# 2_dsub_to_pins_quick.net
KiCad netlist of a schematic drawn in EAGLE
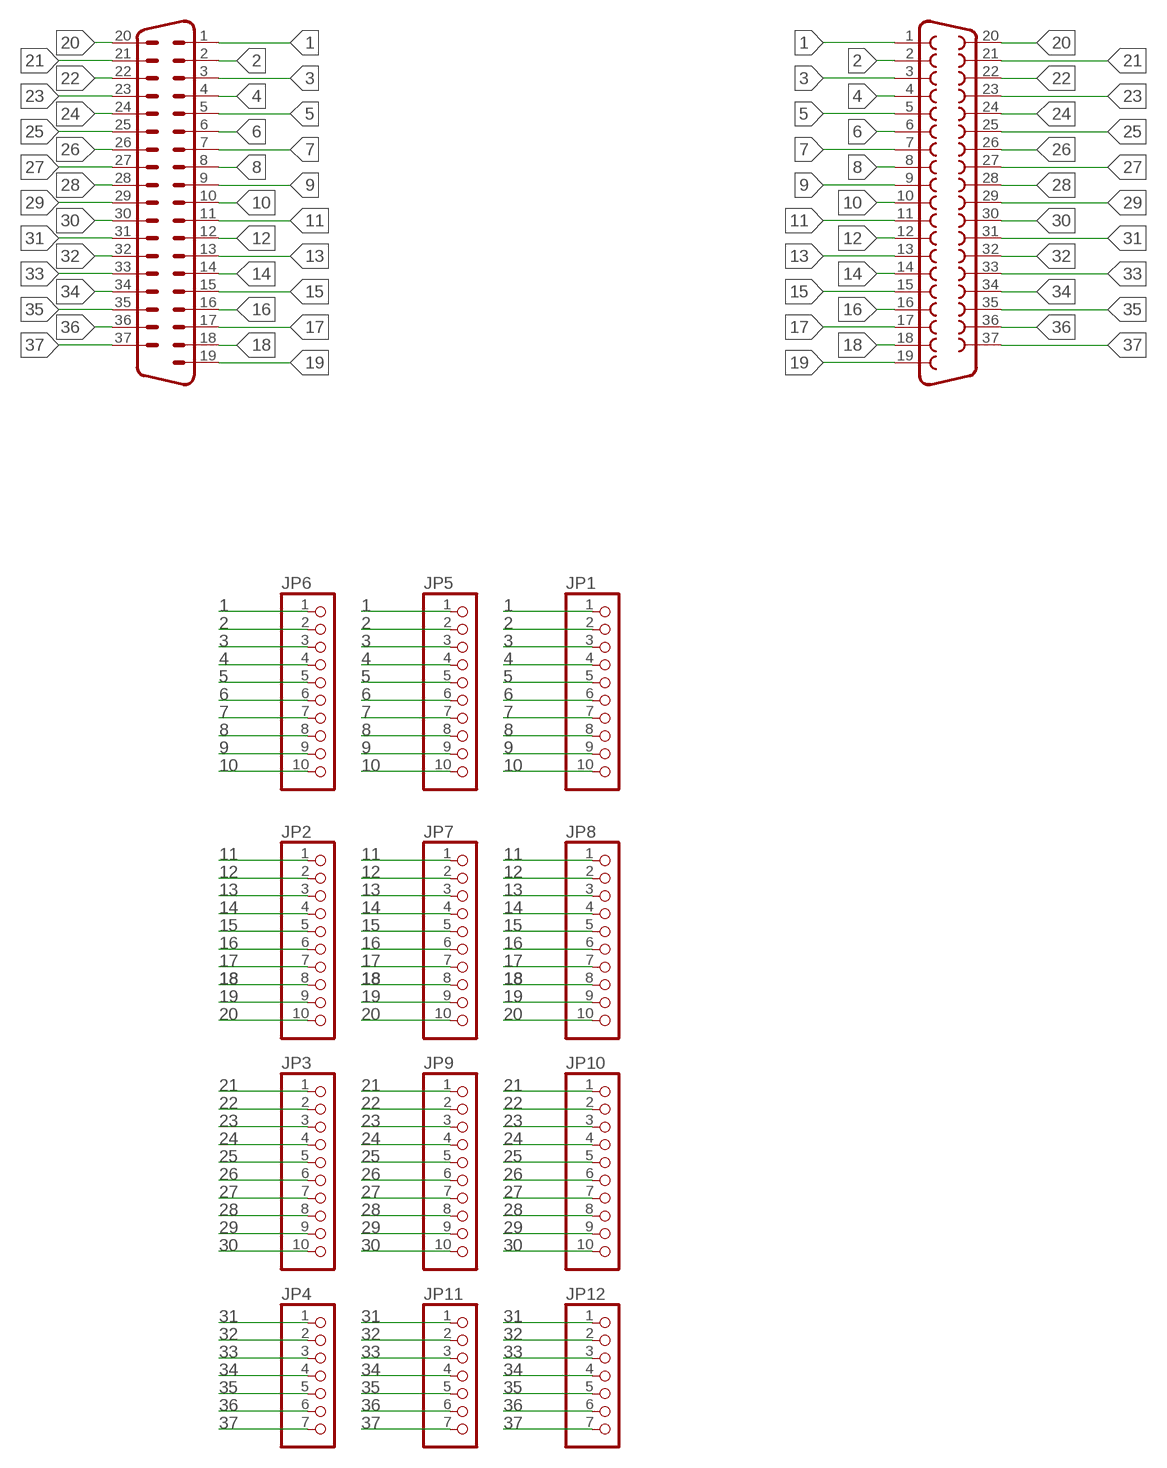
[diagram p0: schematic, sheet 1]

(export (version "E")
  (design (tool "Eeschema 10.0.6"))
  (components
    (comp (ref "JP1")
      (value "PINHD-1X10")
      (footprint "eagle-import:1X10")
      (libsource (lib "eagle-import") (part "PINHD-1X10"))
    )
    (comp (ref "JP2")
      (value "PINHD-1X10")
      (footprint "eagle-import:1X10")
      (libsource (lib "eagle-import") (part "PINHD-1X10"))
    )
    (comp (ref "JP3")
      (value "PINHD-1X10")
      (footprint "eagle-import:1X10")
      (libsource (lib "eagle-import") (part "PINHD-1X10"))
    )
    (comp (ref "JP4")
      (value "PINHD-1X7")
      (footprint "eagle-import:1X07")
      (libsource (lib "eagle-import") (part "PINHD-1X7"))
    )
    (comp (ref "JP5")
      (value "PINHD-1X10")
      (footprint "eagle-import:1X10")
      (libsource (lib "eagle-import") (part "PINHD-1X10"))
    )
    (comp (ref "JP6")
      (value "PINHD-1X10")
      (footprint "eagle-import:1X10")
      (libsource (lib "eagle-import") (part "PINHD-1X10"))
    )
    (comp (ref "JP7")
      (value "PINHD-1X10")
      (footprint "eagle-import:1X10")
      (libsource (lib "eagle-import") (part "PINHD-1X10"))
    )
    (comp (ref "JP8")
      (value "PINHD-1X10")
      (footprint "eagle-import:1X10")
      (libsource (lib "eagle-import") (part "PINHD-1X10"))
    )
    (comp (ref "JP9")
      (value "PINHD-1X10")
      (footprint "eagle-import:1X10")
      (libsource (lib "eagle-import") (part "PINHD-1X10"))
    )
    (comp (ref "JP10")
      (value "PINHD-1X10")
      (footprint "eagle-import:1X10")
      (libsource (lib "eagle-import") (part "PINHD-1X10"))
    )
    (comp (ref "JP11")
      (value "PINHD-1X7")
      (footprint "eagle-import:1X07")
      (libsource (lib "eagle-import") (part "PINHD-1X7"))
    )
    (comp (ref "JP12")
      (value "PINHD-1X7")
      (footprint "eagle-import:1X07")
      (libsource (lib "eagle-import") (part "PINHD-1X7"))
    )
    (comp (ref "X33")
      (value "M37HP")
      (footprint "eagle-import:M37HP")
      (libsource (lib "eagle-import") (part "M37HP"))
    )
    (comp (ref "X34")
      (value "F37HP")
      (footprint "eagle-import:F37HP")
      (libsource (lib "eagle-import") (part "F37HP"))
    )
  )
  (nets
    (net (code "1") (name "1") (class "Default")
      (node (ref "JP1") (pin "1") (pinfunction "1_1") (pintype "passive"))
      (node (ref "JP5") (pin "1") (pinfunction "1_1") (pintype "passive"))
      (node (ref "JP6") (pin "1") (pinfunction "1_1") (pintype "passive"))
      (node (ref "X33") (pin "1") (pinfunction "1_1") (pintype "passive"))
      (node (ref "X34") (pin "1") (pinfunction "1_1") (pintype "passive"))
    )
    (net (code "2") (name "2") (class "Default")
      (node (ref "JP1") (pin "2") (pinfunction "2_2") (pintype "passive"))
      (node (ref "JP5") (pin "2") (pinfunction "2_2") (pintype "passive"))
      (node (ref "JP6") (pin "2") (pinfunction "2_2") (pintype "passive"))
      (node (ref "X33") (pin "2") (pinfunction "2_2") (pintype "passive"))
      (node (ref "X34") (pin "2") (pinfunction "2_2") (pintype "passive"))
    )
    (net (code "3") (name "3") (class "Default")
      (node (ref "JP1") (pin "3") (pinfunction "3_3") (pintype "passive"))
      (node (ref "JP5") (pin "3") (pinfunction "3_3") (pintype "passive"))
      (node (ref "JP6") (pin "3") (pinfunction "3_3") (pintype "passive"))
      (node (ref "X33") (pin "3") (pinfunction "3_3") (pintype "passive"))
      (node (ref "X34") (pin "3") (pinfunction "3_3") (pintype "passive"))
    )
    (net (code "4") (name "4") (class "Default")
      (node (ref "JP1") (pin "4") (pinfunction "4_4") (pintype "passive"))
      (node (ref "JP5") (pin "4") (pinfunction "4_4") (pintype "passive"))
      (node (ref "JP6") (pin "4") (pinfunction "4_4") (pintype "passive"))
      (node (ref "X33") (pin "4") (pinfunction "4_4") (pintype "passive"))
      (node (ref "X34") (pin "4") (pinfunction "4_4") (pintype "passive"))
    )
    (net (code "5") (name "5") (class "Default")
      (node (ref "JP1") (pin "5") (pinfunction "5_5") (pintype "passive"))
      (node (ref "JP5") (pin "5") (pinfunction "5_5") (pintype "passive"))
      (node (ref "JP6") (pin "5") (pinfunction "5_5") (pintype "passive"))
      (node (ref "X33") (pin "5") (pinfunction "5_5") (pintype "passive"))
      (node (ref "X34") (pin "5") (pinfunction "5_5") (pintype "passive"))
    )
    (net (code "6") (name "6") (class "Default")
      (node (ref "JP1") (pin "6") (pinfunction "6_6") (pintype "passive"))
      (node (ref "JP5") (pin "6") (pinfunction "6_6") (pintype "passive"))
      (node (ref "JP6") (pin "6") (pinfunction "6_6") (pintype "passive"))
      (node (ref "X33") (pin "6") (pinfunction "6_6") (pintype "passive"))
      (node (ref "X34") (pin "6") (pinfunction "6_6") (pintype "passive"))
    )
    (net (code "7") (name "7") (class "Default")
      (node (ref "JP1") (pin "7") (pinfunction "7_7") (pintype "passive"))
      (node (ref "JP5") (pin "7") (pinfunction "7_7") (pintype "passive"))
      (node (ref "JP6") (pin "7") (pinfunction "7_7") (pintype "passive"))
      (node (ref "X33") (pin "7") (pinfunction "7_7") (pintype "passive"))
      (node (ref "X34") (pin "7") (pinfunction "7_7") (pintype "passive"))
    )
    (net (code "8") (name "8") (class "Default")
      (node (ref "JP1") (pin "8") (pinfunction "8_8") (pintype "passive"))
      (node (ref "JP5") (pin "8") (pinfunction "8_8") (pintype "passive"))
      (node (ref "JP6") (pin "8") (pinfunction "8_8") (pintype "passive"))
      (node (ref "X33") (pin "8") (pinfunction "8_8") (pintype "passive"))
      (node (ref "X34") (pin "8") (pinfunction "8_8") (pintype "passive"))
    )
    (net (code "9") (name "9") (class "Default")
      (node (ref "JP1") (pin "9") (pinfunction "9_9") (pintype "passive"))
      (node (ref "JP5") (pin "9") (pinfunction "9_9") (pintype "passive"))
      (node (ref "JP6") (pin "9") (pinfunction "9_9") (pintype "passive"))
      (node (ref "X33") (pin "9") (pinfunction "9_9") (pintype "passive"))
      (node (ref "X34") (pin "9") (pinfunction "9_9") (pintype "passive"))
    )
    (net (code "10") (name "10") (class "Default")
      (node (ref "JP1") (pin "10") (pinfunction "10_10") (pintype "passive"))
      (node (ref "JP5") (pin "10") (pinfunction "10_10") (pintype "passive"))
      (node (ref "JP6") (pin "10") (pinfunction "10_10") (pintype "passive"))
      (node (ref "X33") (pin "10") (pinfunction "10_10") (pintype "passive"))
      (node (ref "X34") (pin "10") (pinfunction "10_10") (pintype "passive"))
    )
    (net (code "11") (name "11") (class "Default")
      (node (ref "JP2") (pin "1") (pinfunction "1_1") (pintype "passive"))
      (node (ref "JP7") (pin "1") (pinfunction "1_1") (pintype "passive"))
      (node (ref "JP8") (pin "1") (pinfunction "1_1") (pintype "passive"))
      (node (ref "X33") (pin "11") (pinfunction "11_11") (pintype "passive"))
      (node (ref "X34") (pin "11") (pinfunction "11_11") (pintype "passive"))
    )
    (net (code "12") (name "12") (class "Default")
      (node (ref "JP2") (pin "2") (pinfunction "2_2") (pintype "passive"))
      (node (ref "JP7") (pin "2") (pinfunction "2_2") (pintype "passive"))
      (node (ref "JP8") (pin "2") (pinfunction "2_2") (pintype "passive"))
      (node (ref "X33") (pin "12") (pinfunction "12_12") (pintype "passive"))
      (node (ref "X34") (pin "12") (pinfunction "12_12") (pintype "passive"))
    )
    (net (code "13") (name "13") (class "Default")
      (node (ref "JP2") (pin "3") (pinfunction "3_3") (pintype "passive"))
      (node (ref "JP7") (pin "3") (pinfunction "3_3") (pintype "passive"))
      (node (ref "JP8") (pin "3") (pinfunction "3_3") (pintype "passive"))
      (node (ref "X33") (pin "13") (pinfunction "13_13") (pintype "passive"))
      (node (ref "X34") (pin "13") (pinfunction "13_13") (pintype "passive"))
    )
    (net (code "14") (name "14") (class "Default")
      (node (ref "JP2") (pin "4") (pinfunction "4_4") (pintype "passive"))
      (node (ref "JP7") (pin "4") (pinfunction "4_4") (pintype "passive"))
      (node (ref "JP8") (pin "4") (pinfunction "4_4") (pintype "passive"))
      (node (ref "X33") (pin "14") (pinfunction "14_14") (pintype "passive"))
      (node (ref "X34") (pin "14") (pinfunction "14_14") (pintype "passive"))
    )
    (net (code "15") (name "15") (class "Default")
      (node (ref "JP2") (pin "5") (pinfunction "5_5") (pintype "passive"))
      (node (ref "JP7") (pin "5") (pinfunction "5_5") (pintype "passive"))
      (node (ref "JP8") (pin "5") (pinfunction "5_5") (pintype "passive"))
      (node (ref "X33") (pin "15") (pinfunction "15_15") (pintype "passive"))
      (node (ref "X34") (pin "15") (pinfunction "15_15") (pintype "passive"))
    )
    (net (code "16") (name "16") (class "Default")
      (node (ref "JP2") (pin "6") (pinfunction "6_6") (pintype "passive"))
      (node (ref "JP7") (pin "6") (pinfunction "6_6") (pintype "passive"))
      (node (ref "JP8") (pin "6") (pinfunction "6_6") (pintype "passive"))
      (node (ref "X33") (pin "16") (pinfunction "16_16") (pintype "passive"))
      (node (ref "X34") (pin "16") (pinfunction "16_16") (pintype "passive"))
    )
    (net (code "17") (name "17") (class "Default")
      (node (ref "JP2") (pin "7") (pinfunction "7_7") (pintype "passive"))
      (node (ref "JP7") (pin "7") (pinfunction "7_7") (pintype "passive"))
      (node (ref "JP8") (pin "7") (pinfunction "7_7") (pintype "passive"))
      (node (ref "X33") (pin "17") (pinfunction "17_17") (pintype "passive"))
      (node (ref "X34") (pin "17") (pinfunction "17_17") (pintype "passive"))
    )
    (net (code "18") (name "18") (class "Default")
      (node (ref "JP2") (pin "8") (pinfunction "8_8") (pintype "passive"))
      (node (ref "JP7") (pin "8") (pinfunction "8_8") (pintype "passive"))
      (node (ref "JP8") (pin "8") (pinfunction "8_8") (pintype "passive"))
      (node (ref "X33") (pin "18") (pinfunction "18_18") (pintype "passive"))
      (node (ref "X34") (pin "18") (pinfunction "18_18") (pintype "passive"))
    )
    (net (code "19") (name "19") (class "Default")
      (node (ref "JP2") (pin "9") (pinfunction "9_9") (pintype "passive"))
      (node (ref "JP7") (pin "9") (pinfunction "9_9") (pintype "passive"))
      (node (ref "JP8") (pin "9") (pinfunction "9_9") (pintype "passive"))
      (node (ref "X33") (pin "19") (pinfunction "19_19") (pintype "passive"))
      (node (ref "X34") (pin "19") (pinfunction "19_19") (pintype "passive"))
    )
    (net (code "20") (name "20") (class "Default")
      (node (ref "JP2") (pin "10") (pinfunction "10_10") (pintype "passive"))
      (node (ref "JP7") (pin "10") (pinfunction "10_10") (pintype "passive"))
      (node (ref "JP8") (pin "10") (pinfunction "10_10") (pintype "passive"))
      (node (ref "X33") (pin "20") (pinfunction "20_20") (pintype "passive"))
      (node (ref "X34") (pin "20") (pinfunction "20_20") (pintype "passive"))
    )
    (net (code "21") (name "21") (class "Default")
      (node (ref "JP10") (pin "1") (pinfunction "1_1") (pintype "passive"))
      (node (ref "JP3") (pin "1") (pinfunction "1_1") (pintype "passive"))
      (node (ref "JP9") (pin "1") (pinfunction "1_1") (pintype "passive"))
      (node (ref "X33") (pin "21") (pinfunction "21_21") (pintype "passive"))
      (node (ref "X34") (pin "21") (pinfunction "21_21") (pintype "passive"))
    )
    (net (code "22") (name "22") (class "Default")
      (node (ref "JP10") (pin "2") (pinfunction "2_2") (pintype "passive"))
      (node (ref "JP3") (pin "2") (pinfunction "2_2") (pintype "passive"))
      (node (ref "JP9") (pin "2") (pinfunction "2_2") (pintype "passive"))
      (node (ref "X33") (pin "22") (pinfunction "22_22") (pintype "passive"))
      (node (ref "X34") (pin "22") (pinfunction "22_22") (pintype "passive"))
    )
    (net (code "23") (name "23") (class "Default")
      (node (ref "JP10") (pin "3") (pinfunction "3_3") (pintype "passive"))
      (node (ref "JP3") (pin "3") (pinfunction "3_3") (pintype "passive"))
      (node (ref "JP9") (pin "3") (pinfunction "3_3") (pintype "passive"))
      (node (ref "X33") (pin "23") (pinfunction "23_23") (pintype "passive"))
      (node (ref "X34") (pin "23") (pinfunction "23_23") (pintype "passive"))
    )
    (net (code "24") (name "24") (class "Default")
      (node (ref "JP10") (pin "4") (pinfunction "4_4") (pintype "passive"))
      (node (ref "JP3") (pin "4") (pinfunction "4_4") (pintype "passive"))
      (node (ref "JP9") (pin "4") (pinfunction "4_4") (pintype "passive"))
      (node (ref "X33") (pin "24") (pinfunction "24_24") (pintype "passive"))
      (node (ref "X34") (pin "24") (pinfunction "24_24") (pintype "passive"))
    )
    (net (code "25") (name "25") (class "Default")
      (node (ref "JP10") (pin "5") (pinfunction "5_5") (pintype "passive"))
      (node (ref "JP3") (pin "5") (pinfunction "5_5") (pintype "passive"))
      (node (ref "JP9") (pin "5") (pinfunction "5_5") (pintype "passive"))
      (node (ref "X33") (pin "25") (pinfunction "25_25") (pintype "passive"))
      (node (ref "X34") (pin "25") (pinfunction "25_25") (pintype "passive"))
    )
    (net (code "26") (name "26") (class "Default")
      (node (ref "JP10") (pin "6") (pinfunction "6_6") (pintype "passive"))
      (node (ref "JP3") (pin "6") (pinfunction "6_6") (pintype "passive"))
      (node (ref "JP9") (pin "6") (pinfunction "6_6") (pintype "passive"))
      (node (ref "X33") (pin "26") (pinfunction "26_26") (pintype "passive"))
      (node (ref "X34") (pin "26") (pinfunction "26_26") (pintype "passive"))
    )
    (net (code "27") (name "27") (class "Default")
      (node (ref "JP10") (pin "7") (pinfunction "7_7") (pintype "passive"))
      (node (ref "JP3") (pin "7") (pinfunction "7_7") (pintype "passive"))
      (node (ref "JP9") (pin "7") (pinfunction "7_7") (pintype "passive"))
      (node (ref "X33") (pin "27") (pinfunction "27_27") (pintype "passive"))
      (node (ref "X34") (pin "27") (pinfunction "27_27") (pintype "passive"))
    )
    (net (code "28") (name "28") (class "Default")
      (node (ref "JP10") (pin "8") (pinfunction "8_8") (pintype "passive"))
      (node (ref "JP3") (pin "8") (pinfunction "8_8") (pintype "passive"))
      (node (ref "JP9") (pin "8") (pinfunction "8_8") (pintype "passive"))
      (node (ref "X33") (pin "28") (pinfunction "28_28") (pintype "passive"))
      (node (ref "X34") (pin "28") (pinfunction "28_28") (pintype "passive"))
    )
    (net (code "29") (name "29") (class "Default")
      (node (ref "JP10") (pin "9") (pinfunction "9_9") (pintype "passive"))
      (node (ref "JP3") (pin "9") (pinfunction "9_9") (pintype "passive"))
      (node (ref "JP9") (pin "9") (pinfunction "9_9") (pintype "passive"))
      (node (ref "X33") (pin "29") (pinfunction "29_29") (pintype "passive"))
      (node (ref "X34") (pin "29") (pinfunction "29_29") (pintype "passive"))
    )
    (net (code "30") (name "30") (class "Default")
      (node (ref "JP10") (pin "10") (pinfunction "10_10") (pintype "passive"))
      (node (ref "JP3") (pin "10") (pinfunction "10_10") (pintype "passive"))
      (node (ref "JP9") (pin "10") (pinfunction "10_10") (pintype "passive"))
      (node (ref "X33") (pin "30") (pinfunction "30_30") (pintype "passive"))
      (node (ref "X34") (pin "30") (pinfunction "30_30") (pintype "passive"))
    )
    (net (code "31") (name "31") (class "Default")
      (node (ref "JP11") (pin "1") (pinfunction "1_1") (pintype "passive"))
      (node (ref "JP12") (pin "1") (pinfunction "1_1") (pintype "passive"))
      (node (ref "JP4") (pin "1") (pinfunction "1_1") (pintype "passive"))
      (node (ref "X33") (pin "31") (pinfunction "31_31") (pintype "passive"))
      (node (ref "X34") (pin "31") (pinfunction "31_31") (pintype "passive"))
    )
    (net (code "32") (name "32") (class "Default")
      (node (ref "JP11") (pin "2") (pinfunction "2_2") (pintype "passive"))
      (node (ref "JP12") (pin "2") (pinfunction "2_2") (pintype "passive"))
      (node (ref "JP4") (pin "2") (pinfunction "2_2") (pintype "passive"))
      (node (ref "X33") (pin "32") (pinfunction "32_32") (pintype "passive"))
      (node (ref "X34") (pin "32") (pinfunction "32_32") (pintype "passive"))
    )
    (net (code "33") (name "33") (class "Default")
      (node (ref "JP11") (pin "3") (pinfunction "3_3") (pintype "passive"))
      (node (ref "JP12") (pin "3") (pinfunction "3_3") (pintype "passive"))
      (node (ref "JP4") (pin "3") (pinfunction "3_3") (pintype "passive"))
      (node (ref "X33") (pin "33") (pinfunction "33_33") (pintype "passive"))
      (node (ref "X34") (pin "33") (pinfunction "33_33") (pintype "passive"))
    )
    (net (code "34") (name "34") (class "Default")
      (node (ref "JP11") (pin "4") (pinfunction "4_4") (pintype "passive"))
      (node (ref "JP12") (pin "4") (pinfunction "4_4") (pintype "passive"))
      (node (ref "JP4") (pin "4") (pinfunction "4_4") (pintype "passive"))
      (node (ref "X33") (pin "34") (pinfunction "34_34") (pintype "passive"))
      (node (ref "X34") (pin "34") (pinfunction "34_34") (pintype "passive"))
    )
    (net (code "35") (name "35") (class "Default")
      (node (ref "JP11") (pin "5") (pinfunction "5_5") (pintype "passive"))
      (node (ref "JP12") (pin "5") (pinfunction "5_5") (pintype "passive"))
      (node (ref "JP4") (pin "5") (pinfunction "5_5") (pintype "passive"))
      (node (ref "X33") (pin "35") (pinfunction "35_35") (pintype "passive"))
      (node (ref "X34") (pin "35") (pinfunction "35_35") (pintype "passive"))
    )
    (net (code "36") (name "36") (class "Default")
      (node (ref "JP11") (pin "6") (pinfunction "6_6") (pintype "passive"))
      (node (ref "JP12") (pin "6") (pinfunction "6_6") (pintype "passive"))
      (node (ref "JP4") (pin "6") (pinfunction "6_6") (pintype "passive"))
      (node (ref "X33") (pin "36") (pinfunction "36_36") (pintype "passive"))
      (node (ref "X34") (pin "36") (pinfunction "36_36") (pintype "passive"))
    )
    (net (code "37") (name "37") (class "Default")
      (node (ref "JP11") (pin "7") (pinfunction "7_7") (pintype "passive"))
      (node (ref "JP12") (pin "7") (pinfunction "7_7") (pintype "passive"))
      (node (ref "JP4") (pin "7") (pinfunction "7_7") (pintype "passive"))
      (node (ref "X33") (pin "37") (pinfunction "37_37") (pintype "passive"))
      (node (ref "X34") (pin "37") (pinfunction "37_37") (pintype "passive"))
    )
  )
)
